# Relays.net
KiCad netlist of a schematic drawn in Altium Designer
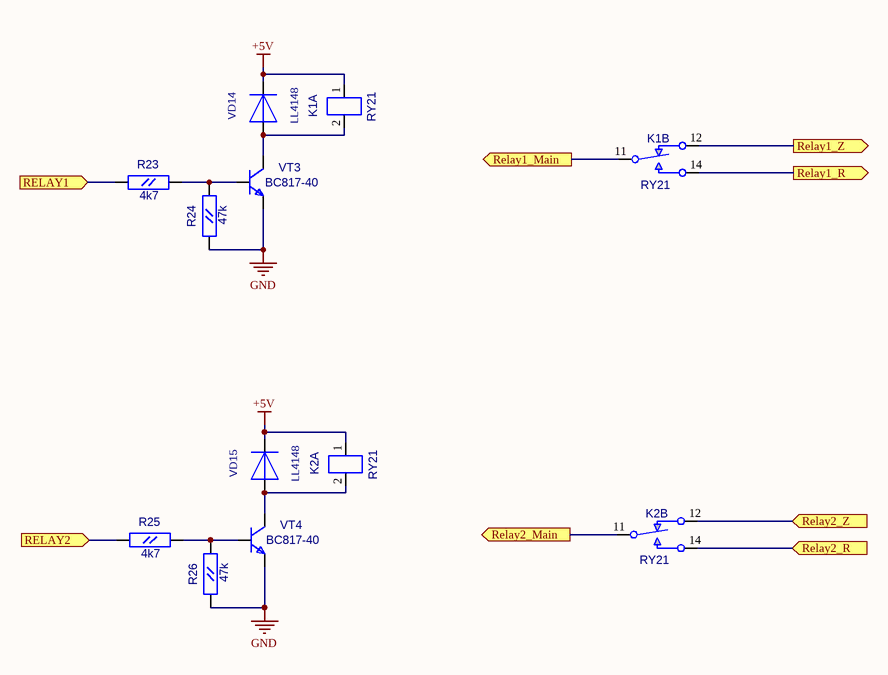
[diagram p0: Relays.SchDoc]

(export (version "E")
  (design (tool "Eeschema 10.0.6"))
  (components
    (comp (ref "K1")
      (value "RY21")
      (footprint "RY21_RY21(Primary)")
      (libsource (lib "shlagbaum") (part "RY21"))
    )
    (comp (ref "K2") (value "RY21") (footprint "RY21_RY21(Primary)") (libsource (lib "") (part "RY21_1")))
    (comp (ref "R23")
      (value "4k7")
      (footprint "RC0603")
      (description "RC0603")
      (libsource (lib "gprs_modem_2") (part "RC0603"))
    )
    (comp (ref "R24")
      (value "47k")
      (footprint "RC0603")
      (description "RC0603")
      (libsource (lib "gprs_modem_2") (part "RC0603"))
    )
    (comp (ref "R25")
      (value "4k7")
      (footprint "RC0603")
      (description "RC0603")
      (libsource (lib "gprs_modem_2") (part "RC0603"))
    )
    (comp (ref "R26")
      (value "47k")
      (footprint "RC0603")
      (description "RC0603")
      (libsource (lib "gprs_modem_2") (part "RC0603"))
    )
    (comp (ref "VD14") (value "LL4148") (footprint "SOD-80") (libsource (lib "gprs_modem_2") (part "LL4148")))
    (comp (ref "VD15") (value "LL4148") (footprint "SOD-80") (libsource (lib "gprs_modem_2") (part "LL4148")))
    (comp (ref "VT3")
      (value "BC817-40")
      (footprint "SOT-23(123)")
      (description "BC846BLT1")
      (libsource (lib "gprs_modem_2") (part "BC846BLT1"))
    )
    (comp (ref "VT4")
      (value "BC817-40")
      (footprint "SOT-23(123)")
      (description "BC846BLT1")
      (libsource (lib "gprs_modem_2") (part "BC846BLT1"))
    )
  )
  (nets
    (net (code "1") (name "+5V") (class "Default")
      (node (ref "K1") (pin "1") (pinfunction "L1_1") (pintype "passive"))
      (node (ref "K2") (pin "1") (pinfunction "L1_1") (pintype "passive"))
      (node (ref "VD14") (pin "2") (pinfunction "+_2") (pintype "passive"))
      (node (ref "VD15") (pin "2") (pinfunction "+_2") (pintype "passive"))
    )
    (net (code "2") (name "/RELAY1") (class "Default")
      (node (ref "R23") (pin "1") (pinfunction "A_1") (pintype "passive"))
    )
    (net (code "3") (name "/RELAY2") (class "Default")
      (node (ref "R25") (pin "1") (pinfunction "A_1") (pintype "passive"))
    )
    (net (code "4") (name "/Relay1_Main") (class "Default")
      (node (ref "K1") (pin "11") (pinfunction "C1_11") (pintype "passive"))
    )
    (net (code "5") (name "/Relay1_R") (class "Default")
      (node (ref "K1") (pin "14") (pinfunction "C2_14") (pintype "passive"))
    )
    (net (code "6") (name "/Relay1_Z") (class "Default")
      (node (ref "K1") (pin "12") (pinfunction "C3_12") (pintype "passive"))
    )
    (net (code "7") (name "/Relay2_Main") (class "Default")
      (node (ref "K2") (pin "11") (pinfunction "C1_11") (pintype "passive"))
    )
    (net (code "8") (name "/Relay2_R") (class "Default")
      (node (ref "K2") (pin "14") (pinfunction "C2_14") (pintype "passive"))
    )
    (net (code "9") (name "/Relay2_Z") (class "Default")
      (node (ref "K2") (pin "12") (pinfunction "C3_12") (pintype "passive"))
    )
    (net (code "10") (name "GND") (class "Default")
      (node (ref "R24") (pin "1") (pinfunction "A_1") (pintype "passive"))
      (node (ref "R26") (pin "1") (pinfunction "A_1") (pintype "passive"))
      (node (ref "VT3") (pin "2") (pinfunction "E_2") (pintype "passive"))
      (node (ref "VT4") (pin "2") (pinfunction "E_2") (pintype "passive"))
    )
    (net (code "11") (name "Net-(K1A-C2)") (class "Default")
      (node (ref "K1") (pin "2") (pinfunction "C2_2") (pintype "passive"))
      (node (ref "VD14") (pin "1") (pinfunction "-_1") (pintype "passive"))
      (node (ref "VT3") (pin "3") (pinfunction "C_3") (pintype "passive"))
    )
    (net (code "12") (name "Net-(K2A-C2)") (class "Default")
      (node (ref "K2") (pin "2") (pinfunction "C2_2") (pintype "passive"))
      (node (ref "VD15") (pin "1") (pinfunction "-_1") (pintype "passive"))
      (node (ref "VT4") (pin "3") (pinfunction "C_3") (pintype "passive"))
    )
    (net (code "13") (name "Net-(R23-B)") (class "Default")
      (node (ref "R23") (pin "2") (pinfunction "B_2") (pintype "passive"))
      (node (ref "R24") (pin "2") (pinfunction "B_2") (pintype "passive"))
      (node (ref "VT3") (pin "1") (pinfunction "B_1") (pintype "passive"))
    )
    (net (code "14") (name "Net-(R25-B)") (class "Default")
      (node (ref "R25") (pin "2") (pinfunction "B_2") (pintype "passive"))
      (node (ref "R26") (pin "2") (pinfunction "B_2") (pintype "passive"))
      (node (ref "VT4") (pin "1") (pinfunction "B_1") (pintype "passive"))
    )
  )
)
